# POWER.net
KiCad netlist of a schematic drawn in Altium Designer
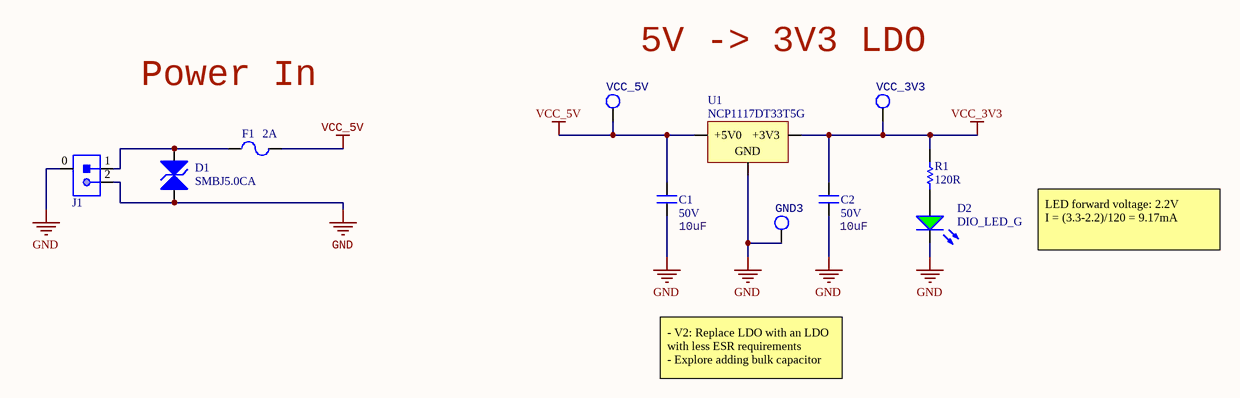
[diagram p0: POWER.SchDoc]

(export (version "E")
  (design (tool "Eeschema 10.0.6"))
  (components
    (comp (ref "C1")
      (value "10uF")
      (footprint "CAPC1206(3216)")
      (description "CAP CER 10UF 50V X5R 1206")
      (fields
        (field (name "MPN") "GRT31CR61H106KE01L")
        (field (name "MANUFACTURER") "Murata")
        (field (name "VOLTAGE RATING") "50V")
      )
      (libsource (lib "UWRT_Schematic_Library_2020") (part "CAP_10uF_50V_1206"))
    )
    (comp (ref "C2")
      (value "10uF")
      (footprint "CAPC1206(3216)")
      (description "CAP CER 10UF 50V X5R 1206")
      (fields
        (field (name "MPN") "GRT31CR61H106KE01L")
        (field (name "MANUFACTURER") "Murata")
        (field (name "VOLTAGE RATING") "50V")
      )
      (libsource (lib "UWRT_Schematic_Library_2020") (part "CAP_10uF_50V_1206"))
    )
    (comp (ref "D1")
      (value "TVS_DIODE_BIDIRECTIONAL")
      (footprint "TVS_DIODE_BIDIRECTIONAL")
      (description "TVS DIODE 5V 9.2V DO214AA")
      (fields (field (name "MANUFACTURER PART NUMBER 1") "SMBJ5.0CA"))
      (libsource (lib "UWRT_Schematic_Library_2020") (part "TVS_DIODE_BIDIRECTIONAL"))
    )
    (comp (ref "D2")
      (value "DIO_LED_G")
      (footprint "LED_0805_LINE")
      (description "LED GREEN DIFFUSED 0805 SMD")
      (fields (field (name "MPN") "LG R971-KN-1") (field (name "MANUFACTURER") "OSRAM"))
      (libsource (lib "UWRT_Schematic_Library_2020") (part "DIO_LED_G"))
    )
    (comp (ref "F1")
      (value "FUSE_2A_0603")
      (footprint "FUSE_0603")
      (description "FUSE SMD 2A 32V")
      (fields (field (name "CURRENT RATING") "2A"))
      (libsource (lib "UWRT_Schematic_Library_2020") (part "FUSE_2A_0603"))
    )
    (comp (ref "GND3")
      (value "TESTPOINT_LOOP")
      (footprint "TESTPOINT_LOOP")
      (description "Loop testpoint through-hole pad")
      (fields (field (name "MANUFACTURER") "Keystone Electronics"))
      (libsource (lib "UWRT_Schematic_Library_2020") (part "TESTPOINT_LOOP"))
    )
    (comp (ref "J1")
      (value "CON_2M_SM_RA")
      (footprint "MOLEX-5024940270")
      (description "CONN HEADER SMD RIGHT ANGLE 2MM PITCH")
      (libsource (lib "UWRT_Schematic_Library_2020") (part "CON_2M_SM_RA"))
    )
    (comp (ref "R1")
      (value "120R")
      (footprint "RESC0603(1608)_N")
      (description "RES SMD 120 OHM 5% 1/10W 0603")
      (fields (field (name "TOLERANCE") "5%") (field (name "MANUFACTURER") "Yageo"))
      (libsource (lib "UWRT_Schematic_Library_2020") (part "RES_120R_0603"))
    )
    (comp (ref "U1")
      (value "5V0_3V3_LDO")
      (footprint "VOLTAGE_REGULATOR")
      (description "IC REG LINEAR 3.3V 1A DPAK")
      (fields (field (name "MPN") "NCP1117DT33T5G") (field (name "MANUFACTURER") "ON Semiconductor"))
      (libsource (lib "UWRT_Schematic_Library_2020") (part "5V0_3V3_LDO"))
    )
    (comp (ref "VCC_3V3")
      (value "TESTPOINT_LOOP")
      (footprint "TESTPOINT_LOOP")
      (description "Loop testpoint through-hole pad")
      (fields (field (name "MANUFACTURER") "Keystone Electronics"))
      (libsource (lib "UWRT_Schematic_Library_2020") (part "TESTPOINT_LOOP"))
    )
    (comp (ref "VCC_5V")
      (value "TESTPOINT_LOOP")
      (footprint "TESTPOINT_LOOP")
      (description "Loop testpoint through-hole pad")
      (fields (field (name "MANUFACTURER") "Keystone Electronics"))
      (libsource (lib "UWRT_Schematic_Library_2020") (part "TESTPOINT_LOOP"))
    )
  )
  (nets
    (net (code "1") (name "GND") (class "Default")
      (node (ref "C1") (pin "2") (pinfunction "2_2") (pintype "passive"))
      (node (ref "C2") (pin "2") (pinfunction "2_2") (pintype "passive"))
      (node (ref "D1") (pin "2") (pinfunction "2_2") (pintype "passive"))
      (node (ref "D2") (pin "2") (pinfunction "K_2") (pintype "passive"))
      (node (ref "GND3") (pin "1") (pintype "passive"))
      (node (ref "J1") (pin "0") (pinfunction "0_0") (pintype "passive"))
      (node (ref "J1") (pin "2") (pinfunction "2_2") (pintype "passive"))
      (node (ref "U1") (pin "1") (pinfunction "GND_1") (pintype "passive"))
    )
    (net (code "2") (name "Net-(D1-Pad1)") (class "Default")
      (node (ref "D1") (pin "1") (pinfunction "1_1") (pintype "passive"))
      (node (ref "F1") (pin "1") (pinfunction "1_1") (pintype "passive"))
      (node (ref "J1") (pin "1") (pinfunction "1_1") (pintype "passive"))
    )
    (net (code "3") (name "Net-(D2-A)") (class "Default")
      (node (ref "D2") (pin "1") (pinfunction "A_1") (pintype "passive"))
      (node (ref "R1") (pin "1") (pinfunction "1_1") (pintype "passive"))
    )
    (net (code "4") (name "VCC_3V3") (class "Default")
      (node (ref "C2") (pin "1") (pinfunction "1_1") (pintype "passive"))
      (node (ref "R1") (pin "2") (pinfunction "2_2") (pintype "passive"))
      (node (ref "U1") (pin "2") (pinfunction "+3V3_2") (pintype "passive"))
      (node (ref "VCC_3V3") (pin "1") (pintype "passive"))
    )
    (net (code "5") (name "VCC_5V") (class "Default")
      (node (ref "C1") (pin "1") (pinfunction "1_1") (pintype "passive"))
      (node (ref "F1") (pin "2") (pinfunction "2_2") (pintype "passive"))
      (node (ref "U1") (pin "3") (pinfunction "+5V0_3") (pintype "passive"))
      (node (ref "VCC_5V") (pin "1") (pintype "passive"))
    )
  )
)
